# LDM_POWER_PCB.net
KiCad netlist of a schematic drawn in Altium Designer
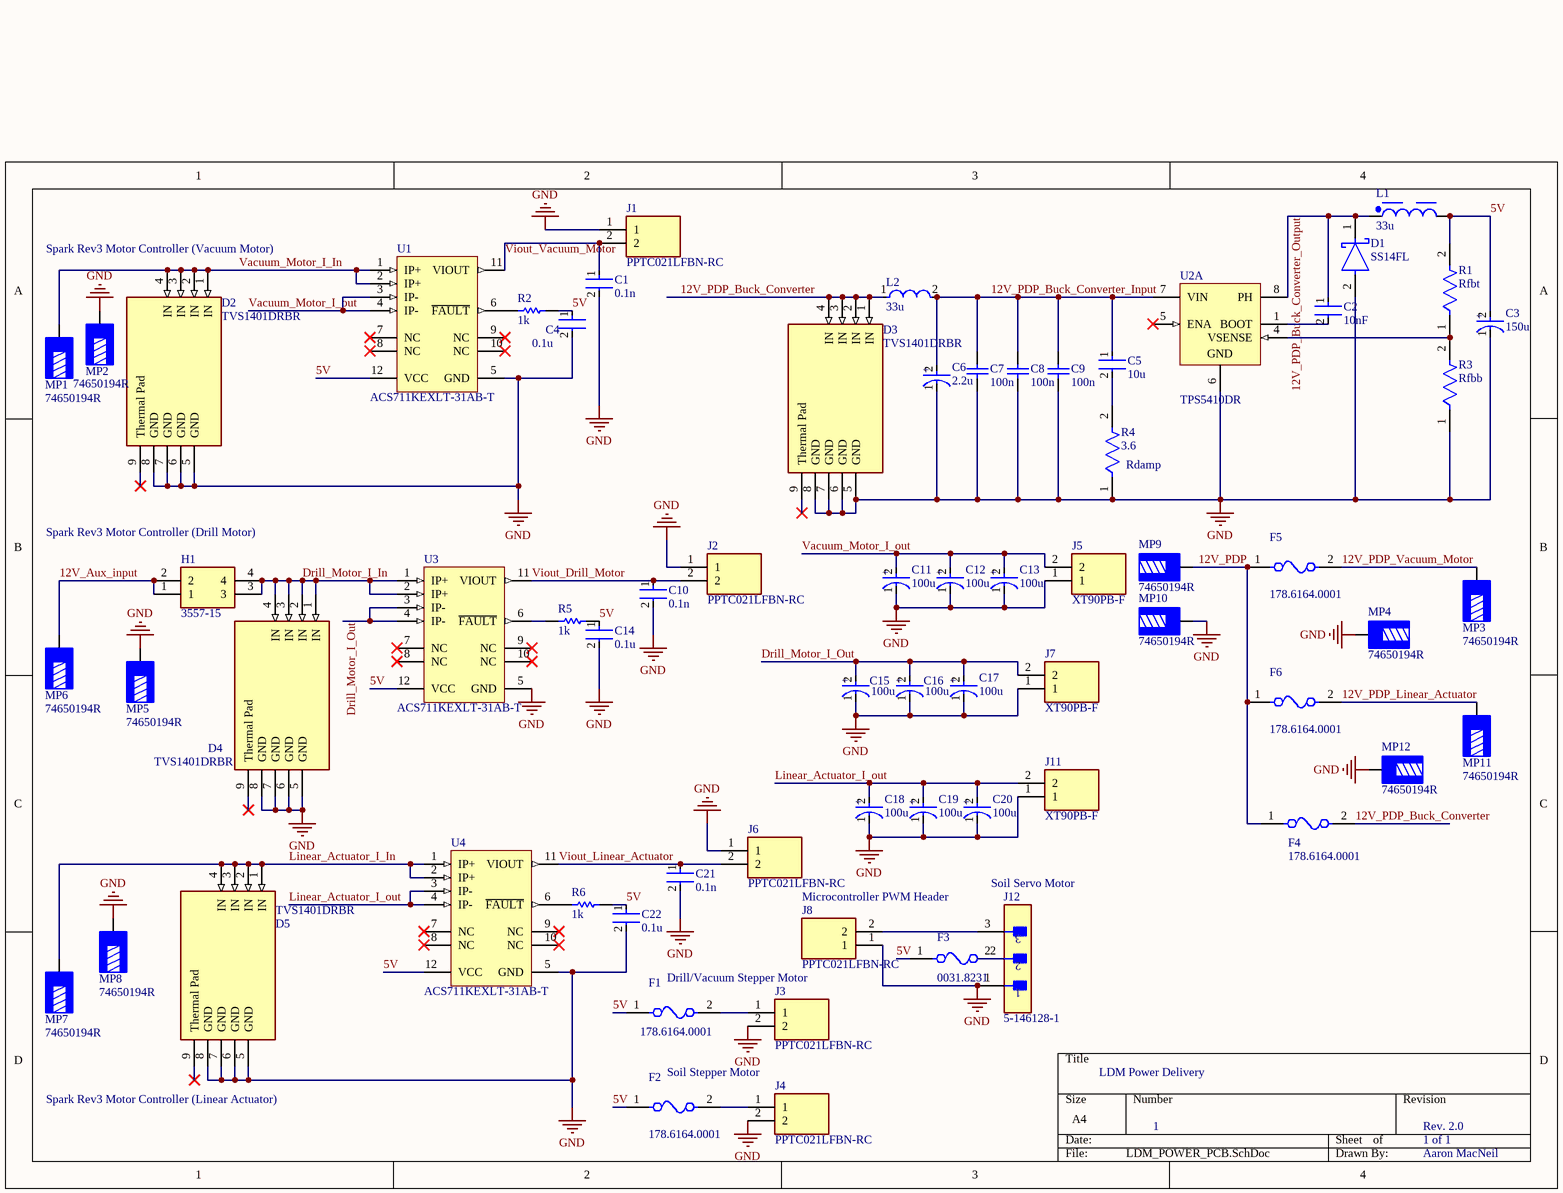
[diagram p0: LDM_POWER_PCB.SchDoc]

(export (version "E")
  (design (tool "Eeschema 10.0.6"))
  (components
    (comp (ref "C1")
      (value "0.1n")
      (footprint "FP-GCM155-0_05-IPC_C")
      (description "Ceramic Capacitor for Automotive 100pF ±5% 50VDC C0G 0402 Paper T/R")
      (fields (field (name "VOLTAGE") "50V") (field (name "TOLERANCE") "5%"))
      (libsource (lib "Altium Content Vault") (part "02cd4be3c70576c341d710602a673aa"))
    )
    (comp (ref "C2")
      (value "10nF")
      (footprint "FP-0805-L_2_01_0_2-W_1_25-IPC_A")
      (description "General Purpose Ceramic Capacitor, 0805, 10nF, 10%, X7R, 0.15, 50V")
      (fields (field (name "TOLERANCE") "10%") (field (name "VOLTAGE") "50V"))
      (libsource (lib "Altium Content Vault") (part "02cd4be3c70576c341d710602a673aa"))
    )
    (comp (ref "C3")
      (value "150u")
      (footprint "FP-POSCAP-B15G-MFG")
      (description "Molded Tantalum Polymer Capacitor 150uF 20% 6.3V life 1000Hours SMD 1411")
      (fields (field (name "TOLERANCE") "20%") (field (name "VOLTAGE") "6.3V"))
      (libsource (lib "Altium Content Vault") (part "203bc49f2ac43e59fd269a8c329ed05"))
    )
    (comp (ref "C4")
      (value "0.1u")
      (footprint "FP-GRM033-0_03-MFG")
      (description "Chip Multilayer Ceramic Capacitors for General Purpose, 0201, 0.10uF, X5R, 15%, 10%, 6.3V")
      (fields (field (name "VOLTAGE") "6.3V") (field (name "TOLERANCE") "10%"))
      (libsource (lib "Altium Content Vault") (part "b4654b650e69147ec39a6b967a45e02"))
    )
    (comp (ref "C5")
      (value "10u")
      (footprint "FP-GRM31C-0_2-e0_3_0_8-MFG")
      (description "Chip Multilayer Ceramic Capacitors for General Purpose, 1206, 10uF, X7R, 15%, 10%, 25V")
      (fields (field (name "TOLERANCE") "10%") (field (name "VOLTAGE") "25V"))
      (libsource (lib "Altium Content Vault") (part "02cd4be3c70576c341d710602a673aa"))
    )
    (comp (ref "C6")
      (value "2.2u")
      (footprint "FP-TAJT-MFG")
      (description "2.2uF 25V  ±10% 4.5Ω 1210  SMD Tantalum Capacitor")
      (fields (field (name "TOLERANCE") "10%"))
      (libsource (lib "Altium Content Vault") (part "203bc49f2ac43e59fd269a8c329ed05"))
    )
    (comp (ref "C7")
      (value "100n")
      (footprint "CAPC2013X145X48NL20T23")
      (fields (field (name "MANUFACTURER") "Vitramon") (field (name "PART NUMBER") "VJ0805Y104KXXAT"))
      (libsource (lib "Altium Content Vault") (part "CAP"))
    )
    (comp (ref "C8")
      (value "100n")
      (footprint "CAPC2013X145X48NL20T23")
      (fields (field (name "MANUFACTURER") "Vitramon") (field (name "PART NUMBER") "VJ0805Y104KXXAT"))
      (libsource (lib "Altium Content Vault") (part "CAP"))
    )
    (comp (ref "C9")
      (value "100n")
      (footprint "CAPC2013X145X48NL20T23")
      (fields (field (name "MANUFACTURER") "Vitramon") (field (name "PART NUMBER") "VJ0805Y104KXXAT"))
      (libsource (lib "Altium Content Vault") (part "CAP"))
    )
    (comp (ref "C10")
      (value "0.1n")
      (footprint "FP-GCM155-0_05-IPC_C")
      (description "Ceramic Capacitor for Automotive 100pF ±5% 50VDC C0G 0402 Paper T/R")
      (fields (field (name "VOLTAGE") "50V") (field (name "TOLERANCE") "5%"))
      (libsource (lib "Altium Content Vault") (part "02cd4be3c70576c341d710602a673aa"))
    )
    (comp (ref "C11")
      (value "100u")
      (footprint "FP-A700X107M12RATE012-MFG")
      (description "ALU POLY SMD 7343 100UF 20% 12.5")
      (fields (field (name "TOLERANCE") "20%"))
      (libsource (lib "Altium Content Vault") (part "cf48714ba7e38822c1575c7ec0b6d1f"))
    )
    (comp (ref "C12")
      (value "100u")
      (footprint "FP-A700X107M12RATE012-MFG")
      (description "ALU POLY SMD 7343 100UF 20% 12.5")
      (fields (field (name "TOLERANCE") "20%"))
      (libsource (lib "Altium Content Vault") (part "cf48714ba7e38822c1575c7ec0b6d1f"))
    )
    (comp (ref "C13")
      (value "100u")
      (footprint "FP-A700X107M12RATE012-MFG")
      (description "ALU POLY SMD 7343 100UF 20% 12.5")
      (fields (field (name "TOLERANCE") "20%"))
      (libsource (lib "Altium Content Vault") (part "cf48714ba7e38822c1575c7ec0b6d1f"))
    )
    (comp (ref "C14")
      (value "0.1u")
      (footprint "FP-GRM033-0_03-MFG")
      (description "Chip Multilayer Ceramic Capacitors for General Purpose, 0201, 0.10uF, X5R, 15%, 10%, 6.3V")
      (fields (field (name "VOLTAGE") "6.3V") (field (name "TOLERANCE") "10%"))
      (libsource (lib "Altium Content Vault") (part "b4654b650e69147ec39a6b967a45e02"))
    )
    (comp (ref "C15")
      (value "100u")
      (footprint "FP-A700X107M12RATE012-MFG")
      (description "ALU POLY SMD 7343 100UF 20% 12.5")
      (fields (field (name "TOLERANCE") "20%"))
      (libsource (lib "Altium Content Vault") (part "cf48714ba7e38822c1575c7ec0b6d1f"))
    )
    (comp (ref "C16")
      (value "100u")
      (footprint "FP-A700X107M12RATE012-MFG")
      (description "ALU POLY SMD 7343 100UF 20% 12.5")
      (fields (field (name "TOLERANCE") "20%"))
      (libsource (lib "Altium Content Vault") (part "cf48714ba7e38822c1575c7ec0b6d1f"))
    )
    (comp (ref "C17")
      (value "100u")
      (footprint "FP-A700X107M12RATE012-MFG")
      (description "ALU POLY SMD 7343 100UF 20% 12.5")
      (fields (field (name "TOLERANCE") "20%"))
      (libsource (lib "Altium Content Vault") (part "cf48714ba7e38822c1575c7ec0b6d1f"))
    )
    (comp (ref "C18")
      (value "100u")
      (footprint "FP-A700X107M12RATE012-MFG")
      (description "ALU POLY SMD 7343 100UF 20% 12.5")
      (fields (field (name "TOLERANCE") "20%"))
      (libsource (lib "Altium Content Vault") (part "cf48714ba7e38822c1575c7ec0b6d1f"))
    )
    (comp (ref "C19")
      (value "100u")
      (footprint "FP-A700X107M12RATE012-MFG")
      (description "ALU POLY SMD 7343 100UF 20% 12.5")
      (fields (field (name "TOLERANCE") "20%"))
      (libsource (lib "Altium Content Vault") (part "cf48714ba7e38822c1575c7ec0b6d1f"))
    )
    (comp (ref "C20")
      (value "100u")
      (footprint "FP-A700X107M12RATE012-MFG")
      (description "ALU POLY SMD 7343 100UF 20% 12.5")
      (fields (field (name "TOLERANCE") "20%"))
      (libsource (lib "Altium Content Vault") (part "cf48714ba7e38822c1575c7ec0b6d1f"))
    )
    (comp (ref "C21")
      (value "0.1n")
      (footprint "FP-GCM155-0_05-IPC_C")
      (description "Ceramic Capacitor for Automotive 100pF ±5% 50VDC C0G 0402 Paper T/R")
      (fields (field (name "VOLTAGE") "50V") (field (name "TOLERANCE") "5%"))
      (libsource (lib "Altium Content Vault") (part "02cd4be3c70576c341d710602a673aa"))
    )
    (comp (ref "C22")
      (value "0.1u")
      (footprint "FP-GRM033-0_03-MFG")
      (description "Chip Multilayer Ceramic Capacitors for General Purpose, 0201, 0.10uF, X5R, 15%, 10%, 6.3V")
      (fields (field (name "VOLTAGE") "6.3V") (field (name "TOLERANCE") "10%"))
      (libsource (lib "Altium Content Vault") (part "b4654b650e69147ec39a6b967a45e02"))
    )
    (comp (ref "D1")
      (value "SS14FL")
      (footprint "FP-425AD-MFG")
      (description "DIODE SCHOTTKY 40V 1A SOD123F")
      (fields
        (field (name "MANUFACTURER") "ON Semiconductor")
        (field (name "OCTOPART") "https://octopart.com/ss14fl-on+semiconductor-84331601")
      )
      (libsource (lib "Altium Content Vault") (part "c1678fac7984e62e0809fbf79c06691"))
    )
    (comp (ref "D2")
      (value "TVS1401DRBR")
      (footprint "FP-DRB0008A-MFG")
      (description "IC UNIDIR PRECISION SURGE DIODE")
      (libsource (lib "Altium Content Vault") (part "760ea3fe8f6653726833b70eb34efed"))
    )
    (comp (ref "D3")
      (value "TVS1401DRBR")
      (footprint "FP-DRB0008A-MFG")
      (description "IC UNIDIR PRECISION SURGE DIODE")
      (libsource (lib "Altium Content Vault") (part "760ea3fe8f6653726833b70eb34efed"))
    )
    (comp (ref "D4")
      (value "TVS1401DRBR")
      (footprint "FP-DRB0008A-MFG")
      (description "IC UNIDIR PRECISION SURGE DIODE")
      (libsource (lib "Altium Content Vault") (part "760ea3fe8f6653726833b70eb34efed"))
    )
    (comp (ref "D5")
      (value "TVS1401DRBR")
      (footprint "FP-DRB0008A-MFG")
      (description "IC UNIDIR PRECISION SURGE DIODE")
      (libsource (lib "Altium Content Vault") (part "760ea3fe8f6653726833b70eb34efed"))
    )
    (comp (ref "F1")
      (value "178.6164.0001")
      (footprint "FP-178_6164_0001-MFG")
      (description "FUSE HOLDER BLADE 80V PCB")
      (fields
        (field (name "MANUFACTURER") "Littelfuse Inc")
        (field (name "OCTOPART") "https://octopart.com/178.6164.0001-littelfuse-44502275")
      )
      (libsource (lib "Altium Content Vault") (part "5bcf9b9f640e542cf0359d10258e979"))
    )
    (comp (ref "F2")
      (value "178.6164.0001")
      (footprint "FP-178_6164_0001-MFG")
      (description "FUSE HOLDER BLADE 80V PCB")
      (fields
        (field (name "MANUFACTURER") "Littelfuse Inc")
        (field (name "OCTOPART") "https://octopart.com/178.6164.0001-littelfuse-44502275")
      )
      (libsource (lib "Altium Content Vault") (part "5bcf9b9f640e542cf0359d10258e979"))
    )
    (comp (ref "F3")
      (value "0031.8231")
      (footprint "FP-0031_8231-MFG")
      (description "FUSE BLOK CARTRIDGE 600V 16A PCB")
      (fields
        (field (name "OCTOPART") "https://octopart.com/0031.8231-schurter-8659")
        (field (name "MANUFACTURER") "Schurter")
      )
      (libsource (lib "Altium Content Vault") (part "5bcf9b9f640e542cf0359d10258e979"))
    )
    (comp (ref "F4")
      (value "178.6164.0001")
      (footprint "FP-178_6164_0001-MFG")
      (description "FUSE HOLDER BLADE 80V PCB")
      (fields
        (field (name "MANUFACTURER") "Littelfuse Inc")
        (field (name "OCTOPART") "https://octopart.com/178.6164.0001-littelfuse-44502275")
      )
      (libsource (lib "Altium Content Vault") (part "5bcf9b9f640e542cf0359d10258e979"))
    )
    (comp (ref "F5")
      (value "178.6164.0001")
      (footprint "FP-178_6164_0001-MFG")
      (description "FUSE HOLDER BLADE 80V PCB")
      (fields
        (field (name "MANUFACTURER") "Littelfuse Inc")
        (field (name "OCTOPART") "https://octopart.com/178.6164.0001-littelfuse-44502275")
      )
      (libsource (lib "Altium Content Vault") (part "5bcf9b9f640e542cf0359d10258e979"))
    )
    (comp (ref "F6")
      (value "178.6164.0001")
      (footprint "FP-178_6164_0001-MFG")
      (description "FUSE HOLDER BLADE 80V PCB")
      (fields
        (field (name "MANUFACTURER") "Littelfuse Inc")
        (field (name "OCTOPART") "https://octopart.com/178.6164.0001-littelfuse-44502275")
      )
      (libsource (lib "Altium Content Vault") (part "5bcf9b9f640e542cf0359d10258e979"))
    )
    (comp (ref "H1")
      (value "3557-15")
      (footprint "SamacSys:355715")
      (description "Hardware")
      (fields (field (name "MOUSER PART NUMBER") "534-3557-15"))
      (libsource (lib "*") (part "3557-15"))
    )
    (comp (ref "J1")
      (value "PPTC021LFBN-RC")
      (footprint "SamacSys:RHDR2W80P0X254_1X2_558X254X850P")
      (description "Connector")
      (libsource (lib "*") (part "PPTC021LFBN-RC"))
    )
    (comp (ref "J2")
      (value "PPTC021LFBN-RC")
      (footprint "SamacSys:RHDR2W80P0X254_1X2_558X254X850P")
      (description "Connector")
      (libsource (lib "*") (part "PPTC021LFBN-RC"))
    )
    (comp (ref "J3")
      (value "PPTC021LFBN-RC")
      (footprint "SamacSys:RHDR2W80P0X254_1X2_558X254X850P")
      (description "Connector")
      (libsource (lib "*") (part "PPTC021LFBN-RC"))
    )
    (comp (ref "J4")
      (value "PPTC021LFBN-RC")
      (footprint "SamacSys:RHDR2W80P0X254_1X2_558X254X850P")
      (description "Connector")
      (libsource (lib "*") (part "PPTC021LFBN-RC"))
    )
    (comp (ref "J5")
      (value "XT90PB-F")
      (footprint "SamacSys:XT90PBF")
      (description "Connector")
      (libsource (lib "*") (part "XT90PB-F"))
    )
    (comp (ref "J6")
      (value "PPTC021LFBN-RC")
      (footprint "SamacSys:RHDR2W80P0X254_1X2_558X254X850P")
      (description "Connector")
      (libsource (lib "*") (part "PPTC021LFBN-RC"))
    )
    (comp (ref "J7")
      (value "XT90PB-F")
      (footprint "SamacSys:XT90PBF")
      (description "Connector")
      (libsource (lib "*") (part "XT90PB-F"))
    )
    (comp (ref "J8")
      (value "PPTC021LFBN-RC")
      (footprint "SamacSys:RHDR2W80P0X254_1X2_558X254X850P")
      (description "Connector")
      (libsource (lib "") (part "PPTC021LFBN-RC_1"))
    )
    (comp (ref "J11")
      (value "XT90PB-F")
      (footprint "SamacSys:XT90PBF")
      (description "Connector")
      (libsource (lib "*") (part "XT90PB-F"))
    )
    (comp (ref "J12")
      (value "5-146128-1")
      (footprint "FP-5-146128-1-MFG")
      (description "CONN HEADER SMD 3POS 2.54MM")
      (fields
        (field (name "MANUFACTURER") "TE")
        (field (name "OCTOPART") "https://octopart.com/5-146128-1-te+connectivity-40948200")
      )
      (libsource (lib "Altium Content Vault") (part "0d3f023dd272f625e17a2be33dea85f"))
    )
    (comp (ref "L1")
      (value "33u")
      (footprint "WE-LQS_6045")
      (fields (field (name "TOLERANCE") "20%"))
      (libsource (lib "Altium Content Vault") (part "Inductor - 2"))
    )
    (comp (ref "L2")
      (value "33u")
      (footprint "FP-NR6028-MFG")
      (description "SMD Power Inductors 33uH ±20% 1.1A 0.286Ω")
      (fields (field (name "TOLERANCE") "20%"))
      (libsource (lib "Altium Content Vault") (part "725321dda6339637d4d059423bc1c3c"))
    )
    (comp (ref "MP1")
      (value "74650194R")
      (footprint "74650194")
      (description "74650194R Bush, THR, internal blind-hole thread, 10 mm W x 7 mm H, M4, 9 Pins")
      (libsource (lib "Altium Content Vault") (part "WP-THRBU_blind hole"))
    )
    (comp (ref "MP2")
      (value "74650194R")
      (footprint "74650194")
      (description "74650194R Bush, THR, internal blind-hole thread, 10 mm W x 7 mm H, M4, 9 Pins")
      (libsource (lib "Altium Content Vault") (part "WP-THRBU_blind hole"))
    )
    (comp (ref "MP3")
      (value "74650194R")
      (footprint "74650194")
      (description "74650194R Bush, THR, internal blind-hole thread, 10 mm W x 7 mm H, M4, 9 Pins")
      (libsource (lib "Altium Content Vault") (part "WP-THRBU_blind hole"))
    )
    (comp (ref "MP4")
      (value "74650194R")
      (footprint "74650194")
      (description "74650194R Bush, THR, internal blind-hole thread, 10 mm W x 7 mm H, M4, 9 Pins")
      (libsource (lib "Altium Content Vault") (part "WP-THRBU_blind hole"))
    )
    (comp (ref "MP5")
      (value "74650194R")
      (footprint "74650194")
      (description "74650194R Bush, THR, internal blind-hole thread, 10 mm W x 7 mm H, M4, 9 Pins")
      (libsource (lib "Altium Content Vault") (part "WP-THRBU_blind hole"))
    )
    (comp (ref "MP6")
      (value "74650194R")
      (footprint "74650194")
      (description "74650194R Bush, THR, internal blind-hole thread, 10 mm W x 7 mm H, M4, 9 Pins")
      (libsource (lib "Altium Content Vault") (part "WP-THRBU_blind hole"))
    )
    (comp (ref "MP7")
      (value "74650194R")
      (footprint "74650194")
      (description "74650194R Bush, THR, internal blind-hole thread, 10 mm W x 7 mm H, M4, 9 Pins")
      (libsource (lib "Altium Content Vault") (part "WP-THRBU_blind hole"))
    )
    (comp (ref "MP8")
      (value "74650194R")
      (footprint "74650194")
      (description "74650194R Bush, THR, internal blind-hole thread, 10 mm W x 7 mm H, M4, 9 Pins")
      (libsource (lib "Altium Content Vault") (part "WP-THRBU_blind hole"))
    )
    (comp (ref "MP9")
      (value "74650194R")
      (footprint "74650194")
      (description "74650194R Bush, THR, internal blind-hole thread, 10 mm W x 7 mm H, M4, 9 Pins")
      (libsource (lib "Altium Content Vault") (part "WP-THRBU_blind hole"))
    )
    (comp (ref "MP10")
      (value "74650194R")
      (footprint "74650194")
      (description "74650194R Bush, THR, internal blind-hole thread, 10 mm W x 7 mm H, M4, 9 Pins")
      (libsource (lib "Altium Content Vault") (part "WP-THRBU_blind hole"))
    )
    (comp (ref "MP11")
      (value "74650194R")
      (footprint "74650194")
      (description "74650194R Bush, THR, internal blind-hole thread, 10 mm W x 7 mm H, M4, 9 Pins")
      (libsource (lib "Altium Content Vault") (part "WP-THRBU_blind hole"))
    )
    (comp (ref "MP12")
      (value "74650194R")
      (footprint "74650194")
      (description "74650194R Bush, THR, internal blind-hole thread, 10 mm W x 7 mm H, M4, 9 Pins")
      (libsource (lib "Altium Content Vault") (part "WP-THRBU_blind hole"))
    )
    (comp (ref "R1")
      (value "Rfbt")
      (footprint "FP-CRCW0402-e3-IPC_B")
      (description "RES SMD 10K OHM 1% 1/16W 0402")
      (fields (field (name "TOLERANCE") "1%"))
      (libsource (lib "Altium Content Vault") (part "1029c3af85768c4190bb7ad29bc67b5"))
    )
    (comp (ref "R2")
      (value "1k")
      (footprint "RESC1608X55X30LL15T15")
      (fields (field (name "PART NUMBER") "ERJ-3EKF1001V") (field (name "MANUFACTURER") "Panasonic"))
      (libsource (lib "Altium Content Vault") (part "RES"))
    )
    (comp (ref "R3")
      (value "Rfbb")
      (footprint "FP-CRCW0402-e3-MFG")
      (description "RES Thick Film, 3.24kΩ, 1%, 0.063W, 100ppm/°C, 0402")
      (fields (field (name "TOLERANCE") "1%"))
      (libsource (lib "Altium Content Vault") (part "1029c3af85768c4190bb7ad29bc67b5"))
    )
    (comp (ref "R4")
      (value "3.6")
      (footprint "FP-ESR10-IPC_A")
      (description "3.6Ω ±5% 0.4W 0805 Anti-Surge Chip Resistor AEC-Q200")
      (fields (field (name "TOLERANCE") "5%"))
      (libsource (lib "Altium Content Vault") (part "1029c3af85768c4190bb7ad29bc67b5"))
    )
    (comp (ref "R5")
      (value "1k")
      (footprint "RESC1608X55X30LL15T15")
      (fields (field (name "PART NUMBER") "ERJ-3EKF1001V") (field (name "MANUFACTURER") "Panasonic"))
      (libsource (lib "Altium Content Vault") (part "RES"))
    )
    (comp (ref "R6")
      (value "1k")
      (footprint "RESC1608X55X30LL15T15")
      (fields (field (name "PART NUMBER") "ERJ-3EKF1001V") (field (name "MANUFACTURER") "Panasonic"))
      (libsource (lib "Altium Content Vault") (part "RES"))
    )
    (comp (ref "U1")
      (value "ACS711KEXLT-31AB-T")
      (footprint "ALEG-EX-12_V")
      (libsource (lib "Altium Content Vault") (part "ALEG-ACS711-QFN-12"))
    )
    (comp (ref "U2")
      (value "TPS5410DR")
      (footprint "D0008A_L")
      (fields (field (name "MANUFACTURER") "Texas Instruments"))
      (libsource (lib "Altium Content Vault") (part "TI-TPS5410D8"))
    )
    (comp (ref "U3")
      (value "ACS711KEXLT-31AB-T")
      (footprint "ALEG-EX-12_V")
      (libsource (lib "Altium Content Vault") (part "ALEG-ACS711-QFN-12"))
    )
    (comp (ref "U4")
      (value "ACS711KEXLT-31AB-T")
      (footprint "ALEG-EX-12_V")
      (libsource (lib "Altium Content Vault") (part "ALEG-ACS711-QFN-12"))
    )
  )
  (nets
    (net (code "1") (name "/5V") (class "Default")
      (node (ref "C14") (pin "1") (pinfunction "1_1") (pintype "passive"))
      (node (ref "C22") (pin "1") (pinfunction "1_1") (pintype "passive"))
      (node (ref "C3") (pin "2") (pinfunction "A_2") (pintype "passive"))
      (node (ref "C4") (pin "1") (pinfunction "1_1") (pintype "passive"))
      (node (ref "F1") (pin "1") (pinfunction "1_1") (pintype "passive"))
      (node (ref "F2") (pin "1") (pinfunction "1_1") (pintype "passive"))
      (node (ref "F3") (pin "1") (pinfunction "1_1") (pintype "passive"))
      (node (ref "L1") (pin "2") (pinfunction "2_2") (pintype "passive"))
      (node (ref "R1") (pin "2") (pinfunction "2_2") (pintype "passive"))
      (node (ref "R2") (pin "2") (pinfunction "2_2") (pintype "passive"))
      (node (ref "R5") (pin "2") (pinfunction "2_2") (pintype "passive"))
      (node (ref "R6") (pin "2") (pinfunction "2_2") (pintype "passive"))
      (node (ref "U1") (pin "12") (pinfunction "VCC_12") (pintype "power_in"))
      (node (ref "U3") (pin "12") (pinfunction "VCC_12") (pintype "power_in"))
      (node (ref "U4") (pin "12") (pinfunction "VCC_12") (pintype "power_in"))
    )
    (net (code "2") (name "/12V_Aux_input") (class "Default")
      (node (ref "H1") (pin "1") (pinfunction "1_1") (pintype "passive"))
      (node (ref "H1") (pin "2") (pinfunction "2_2") (pintype "passive"))
      (node (ref "MP6") (pin "1") (pinfunction "1_1") (pintype "passive"))
    )
    (net (code "3") (name "/12V_PDP") (class "Default")
      (node (ref "F4") (pin "1") (pinfunction "1_1") (pintype "passive"))
      (node (ref "F5") (pin "1") (pinfunction "1_1") (pintype "passive"))
      (node (ref "F6") (pin "1") (pinfunction "1_1") (pintype "passive"))
      (node (ref "MP9") (pin "1") (pinfunction "1_1") (pintype "passive"))
    )
    (net (code "4") (name "/12V_PDP_Buck_Converter") (class "Default")
      (node (ref "D3") (pin "1") (pinfunction "IN_1") (pintype "input"))
      (node (ref "D3") (pin "2") (pinfunction "IN_2") (pintype "input"))
      (node (ref "D3") (pin "3") (pinfunction "IN_3") (pintype "input"))
      (node (ref "D3") (pin "4") (pinfunction "IN_4") (pintype "input"))
      (node (ref "F4") (pin "2") (pinfunction "2_2") (pintype "passive"))
      (node (ref "L2") (pin "1") (pinfunction "1_1") (pintype "passive"))
    )
    (net (code "5") (name "/12V_PDP_Buck_Converter_Input") (class "Default")
      (node (ref "C5") (pin "1") (pinfunction "1_1") (pintype "passive"))
      (node (ref "C6") (pin "2") (pinfunction "A_2") (pintype "passive"))
      (node (ref "C7") (pin "2") (pinfunction "2_2") (pintype "passive"))
      (node (ref "C8") (pin "2") (pinfunction "2_2") (pintype "passive"))
      (node (ref "C9") (pin "2") (pinfunction "2_2") (pintype "passive"))
      (node (ref "L2") (pin "2") (pinfunction "2_2") (pintype "passive"))
      (node (ref "U2") (pin "7") (pinfunction "VIN_7") (pintype "power_in"))
    )
    (net (code "6") (name "/12V_PDP_Buck_Converter_Output") (class "Default")
      (node (ref "C2") (pin "1") (pinfunction "1_1") (pintype "passive"))
      (node (ref "D1") (pin "1") (pinfunction "C_1") (pintype "passive"))
      (node (ref "L1") (pin "1") (pinfunction "1_1") (pintype "passive"))
      (node (ref "U2") (pin "8") (pinfunction "PH_8") (pintype "power_in"))
    )
    (net (code "7") (name "/12V_PDP_Linear_Actuator") (class "Default")
      (node (ref "F6") (pin "2") (pinfunction "2_2") (pintype "passive"))
      (node (ref "MP11") (pin "1") (pinfunction "1_1") (pintype "passive"))
    )
    (net (code "8") (name "/12V_PDP_Vacuum_Motor") (class "Default")
      (node (ref "F5") (pin "2") (pinfunction "2_2") (pintype "passive"))
      (node (ref "MP3") (pin "1") (pinfunction "1_1") (pintype "passive"))
    )
    (net (code "9") (name "/Drill_Motor_I_In") (class "Default")
      (node (ref "D4") (pin "1") (pinfunction "IN_1") (pintype "input"))
      (node (ref "D4") (pin "2") (pinfunction "IN_2") (pintype "input"))
      (node (ref "D4") (pin "3") (pinfunction "IN_3") (pintype "input"))
      (node (ref "D4") (pin "4") (pinfunction "IN_4") (pintype "input"))
      (node (ref "H1") (pin "3") (pinfunction "3_3") (pintype "passive"))
      (node (ref "H1") (pin "4") (pinfunction "4_4") (pintype "passive"))
      (node (ref "U3") (pin "1") (pinfunction "IP+_1") (pintype "input"))
      (node (ref "U3") (pin "2") (pinfunction "IP+_2") (pintype "input"))
    )
    (net (code "10") (name "/Drill_Motor_I_Out") (class "Default")
      (node (ref "C15") (pin "2") (pinfunction "A_2") (pintype "passive"))
      (node (ref "C16") (pin "2") (pinfunction "A_2") (pintype "passive"))
      (node (ref "C17") (pin "2") (pinfunction "A_2") (pintype "passive"))
      (node (ref "J7") (pin "2") (pinfunction "2_2") (pintype "passive"))
      (node (ref "U3") (pin "3") (pinfunction "IP-_3") (pintype "input"))
      (node (ref "U3") (pin "4") (pinfunction "IP-_4") (pintype "input"))
    )
    (net (code "11") (name "/Linear_Actuator_I_In") (class "Default")
      (node (ref "D5") (pin "1") (pinfunction "IN_1") (pintype "input"))
      (node (ref "D5") (pin "2") (pinfunction "IN_2") (pintype "input"))
      (node (ref "D5") (pin "3") (pinfunction "IN_3") (pintype "input"))
      (node (ref "D5") (pin "4") (pinfunction "IN_4") (pintype "input"))
      (node (ref "MP7") (pin "1") (pinfunction "1_1") (pintype "passive"))
      (node (ref "U4") (pin "1") (pinfunction "IP+_1") (pintype "input"))
      (node (ref "U4") (pin "2") (pinfunction "IP+_2") (pintype "input"))
    )
    (net (code "12") (name "/Linear_Actuator_I_out") (class "Default")
      (node (ref "C18") (pin "2") (pinfunction "A_2") (pintype "passive"))
      (node (ref "C19") (pin "2") (pinfunction "A_2") (pintype "passive"))
      (node (ref "C20") (pin "2") (pinfunction "A_2") (pintype "passive"))
      (node (ref "J11") (pin "2") (pinfunction "2_2") (pintype "passive"))
      (node (ref "U4") (pin "3") (pinfunction "IP-_3") (pintype "input"))
      (node (ref "U4") (pin "4") (pinfunction "IP-_4") (pintype "input"))
    )
    (net (code "13") (name "/Vacuum_Motor_I_In") (class "Default")
      (node (ref "D2") (pin "1") (pinfunction "IN_1") (pintype "input"))
      (node (ref "D2") (pin "2") (pinfunction "IN_2") (pintype "input"))
      (node (ref "D2") (pin "3") (pinfunction "IN_3") (pintype "input"))
      (node (ref "D2") (pin "4") (pinfunction "IN_4") (pintype "input"))
      (node (ref "MP1") (pin "1") (pinfunction "1_1") (pintype "passive"))
      (node (ref "U1") (pin "1") (pinfunction "IP+_1") (pintype "input"))
      (node (ref "U1") (pin "2") (pinfunction "IP+_2") (pintype "input"))
    )
    (net (code "14") (name "/Vacuum_Motor_I_out") (class "Default")
      (node (ref "C11") (pin "2") (pinfunction "A_2") (pintype "passive"))
      (node (ref "C12") (pin "2") (pinfunction "A_2") (pintype "passive"))
      (node (ref "C13") (pin "2") (pinfunction "A_2") (pintype "passive"))
      (node (ref "J5") (pin "2") (pinfunction "2_2") (pintype "passive"))
      (node (ref "U1") (pin "3") (pinfunction "IP-_3") (pintype "input"))
      (node (ref "U1") (pin "4") (pinfunction "IP-_4") (pintype "input"))
    )
    (net (code "15") (name "/Viout_Drill_Motor") (class "Default")
      (node (ref "C10") (pin "1") (pinfunction "1_1") (pintype "passive"))
      (node (ref "J2") (pin "2") (pinfunction "2_2") (pintype "passive"))
      (node (ref "U3") (pin "11") (pinfunction "VIOUT_11") (pintype "output"))
    )
    (net (code "16") (name "/Viout_Linear_Actuator") (class "Default")
      (node (ref "C21") (pin "1") (pinfunction "1_1") (pintype "passive"))
      (node (ref "J6") (pin "2") (pinfunction "2_2") (pintype "passive"))
      (node (ref "U4") (pin "11") (pinfunction "VIOUT_11") (pintype "output"))
    )
    (net (code "17") (name "/Viout_Vacuum_Motor") (class "Default")
      (node (ref "C1") (pin "1") (pinfunction "1_1") (pintype "passive"))
      (node (ref "J1") (pin "2") (pinfunction "2_2") (pintype "passive"))
      (node (ref "U1") (pin "11") (pinfunction "VIOUT_11") (pintype "output"))
    )
    (net (code "18") (name "GND") (class "Default")
      (node (ref "C1") (pin "2") (pinfunction "2_2") (pintype "passive"))
      (node (ref "C10") (pin "2") (pinfunction "2_2") (pintype "passive"))
      (node (ref "C11") (pin "1") (pinfunction "C_1") (pintype "passive"))
      (node (ref "C12") (pin "1") (pinfunction "C_1") (pintype "passive"))
      (node (ref "C13") (pin "1") (pinfunction "C_1") (pintype "passive"))
      (node (ref "C14") (pin "2") (pinfunction "2_2") (pintype "passive"))
      (node (ref "C15") (pin "1") (pinfunction "C_1") (pintype "passive"))
      (node (ref "C16") (pin "1") (pinfunction "C_1") (pintype "passive"))
      (node (ref "C17") (pin "1") (pinfunction "C_1") (pintype "passive"))
      (node (ref "C18") (pin "1") (pinfunction "C_1") (pintype "passive"))
      (node (ref "C19") (pin "1") (pinfunction "C_1") (pintype "passive"))
      (node (ref "C20") (pin "1") (pinfunction "C_1") (pintype "passive"))
      (node (ref "C21") (pin "2") (pinfunction "2_2") (pintype "passive"))
      (node (ref "C22") (pin "2") (pinfunction "2_2") (pintype "passive"))
      (node (ref "C3") (pin "1") (pinfunction "C_1") (pintype "passive"))
      (node (ref "C4") (pin "2") (pinfunction "2_2") (pintype "passive"))
      (node (ref "C6") (pin "1") (pinfunction "C_1") (pintype "passive"))
      (node (ref "C7") (pin "1") (pinfunction "1_1") (pintype "passive"))
      (node (ref "C8") (pin "1") (pinfunction "1_1") (pintype "passive"))
      (node (ref "C9") (pin "1") (pinfunction "1_1") (pintype "passive"))
      (node (ref "D1") (pin "2") (pinfunction "A_2") (pintype "passive"))
      (node (ref "D2") (pin "5") (pinfunction "GND_5") (pintype "power_in"))
      (node (ref "D2") (pin "6") (pinfunction "GND_6") (pintype "power_in"))
      (node (ref "D2") (pin "7") (pinfunction "GND_7") (pintype "power_in"))
      (node (ref "D2") (pin "8") (pinfunction "GND_8") (pintype "power_in"))
      (node (ref "D3") (pin "5") (pinfunction "GND_5") (pintype "power_in"))
      (node (ref "D3") (pin "6") (pinfunction "GND_6") (pintype "power_in"))
      (node (ref "D3") (pin "7") (pinfunction "GND_7") (pintype "power_in"))
      (node (ref "D3") (pin "8") (pinfunction "GND_8") (pintype "power_in"))
      (node (ref "D4") (pin "5") (pinfunction "GND_5") (pintype "power_in"))
      (node (ref "D4") (pin "6") (pinfunction "GND_6") (pintype "power_in"))
      (node (ref "D4") (pin "7") (pinfunction "GND_7") (pintype "power_in"))
      (node (ref "D4") (pin "8") (pinfunction "GND_8") (pintype "power_in"))
      (node (ref "D5") (pin "5") (pinfunction "GND_5") (pintype "power_in"))
      (node (ref "D5") (pin "6") (pinfunction "GND_6") (pintype "power_in"))
      (node (ref "D5") (pin "7") (pinfunction "GND_7") (pintype "power_in"))
      (node (ref "D5") (pin "8") (pinfunction "GND_8") (pintype "power_in"))
      (node (ref "J1") (pin "1") (pinfunction "1_1") (pintype "passive"))
      (node (ref "J11") (pin "1") (pinfunction "1_1") (pintype "passive"))
      (node (ref "J12") (pin "1") (pinfunction "1_1") (pintype "passive"))
      (node (ref "J2") (pin "1") (pinfunction "1_1") (pintype "passive"))
      (node (ref "J3") (pin "2") (pinfunction "2_2") (pintype "passive"))
      (node (ref "J4") (pin "2") (pinfunction "2_2") (pintype "passive"))
      (node (ref "J5") (pin "1") (pinfunction "1_1") (pintype "passive"))
      (node (ref "J6") (pin "1") (pinfunction "1_1") (pintype "passive"))
      (node (ref "J7") (pin "1") (pinfunction "1_1") (pintype "passive"))
      (node (ref "J8") (pin "1") (pinfunction "1_1") (pintype "passive"))
      (node (ref "MP10") (pin "1") (pinfunction "1_1") (pintype "passive"))
      (node (ref "MP12") (pin "1") (pinfunction "1_1") (pintype "passive"))
      (node (ref "MP2") (pin "1") (pinfunction "1_1") (pintype "passive"))
      (node (ref "MP4") (pin "1") (pinfunction "1_1") (pintype "passive"))
      (node (ref "MP5") (pin "1") (pinfunction "1_1") (pintype "passive"))
      (node (ref "MP8") (pin "1") (pinfunction "1_1") (pintype "passive"))
      (node (ref "R3") (pin "1") (pinfunction "1_1") (pintype "passive"))
      (node (ref "R4") (pin "1") (pinfunction "1_1") (pintype "passive"))
      (node (ref "U1") (pin "5") (pinfunction "GND_5") (pintype "power_in"))
      (node (ref "U2") (pin "6") (pinfunction "GND_6") (pintype "power_in"))
      (node (ref "U3") (pin "5") (pinfunction "GND_5") (pintype "power_in"))
      (node (ref "U4") (pin "5") (pinfunction "GND_5") (pintype "power_in"))
    )
    (net (code "19") (name "Net-(C5-Pad2)") (class "Default")
      (node (ref "C5") (pin "2") (pinfunction "2_2") (pintype "passive"))
      (node (ref "R4") (pin "2") (pinfunction "2_2") (pintype "passive"))
    )
    (net (code "20") (name "Net-(F1-Pad2)") (class "Default")
      (node (ref "F1") (pin "2") (pinfunction "2_2") (pintype "passive"))
      (node (ref "J3") (pin "1") (pinfunction "1_1") (pintype "passive"))
    )
    (net (code "21") (name "Net-(F2-Pad2)") (class "Default")
      (node (ref "F2") (pin "2") (pinfunction "2_2") (pintype "passive"))
      (node (ref "J4") (pin "1") (pinfunction "1_1") (pintype "passive"))
    )
    (net (code "22") (name "Net-(F3-Pad2)") (class "Default")
      (node (ref "F3") (pin "2") (pinfunction "2_2") (pintype "passive"))
      (node (ref "J12") (pin "2") (pinfunction "2_2") (pintype "passive"))
    )
    (net (code "23") (name "Net-(J12-Pad3)") (class "Default")
      (node (ref "J12") (pin "3") (pinfunction "3_3") (pintype "passive"))
      (node (ref "J8") (pin "2") (pinfunction "2_2") (pintype "passive"))
    )
    (net (code "24") (name "Net-(U1-~{FAULT})") (class "Default")
      (node (ref "R2") (pin "1") (pinfunction "1_1") (pintype "passive"))
      (node (ref "U1") (pin "6") (pinfunction "~{FAULT}_6") (pintype "output"))
    )
    (net (code "25") (name "Net-(U2A-BOOT)") (class "Default")
      (node (ref "C2") (pin "2") (pinfunction "2_2") (pintype "passive"))
      (node (ref "U2") (pin "1") (pinfunction "BOOT_1") (pintype "passive"))
    )
    (net (code "26") (name "Net-(U2A-VSENSE)") (class "Default")
      (node (ref "R1") (pin "1") (pinfunction "1_1") (pintype "passive"))
      (node (ref "R3") (pin "2") (pinfunction "2_2") (pintype "passive"))
      (node (ref "U2") (pin "4") (pinfunction "VSENSE_4") (pintype "input"))
    )
    (net (code "27") (name "Net-(U3-~{FAULT})") (class "Default")
      (node (ref "R5") (pin "1") (pinfunction "1_1") (pintype "passive"))
      (node (ref "U3") (pin "6") (pinfunction "~{FAULT}_6") (pintype "output"))
    )
    (net (code "28") (name "Net-(U4-~{FAULT})") (class "Default")
      (node (ref "R6") (pin "1") (pinfunction "1_1") (pintype "passive"))
      (node (ref "U4") (pin "6") (pinfunction "~{FAULT}_6") (pintype "output"))
    )
    (net (code "29") (name "unconnected-(D2-Thermal_Pad-Pad9)") (class "Default")
      (node (ref "D2") (pin "9") (pinfunction "Thermal_Pad_9") (pintype "power_in+no_connect"))
    )
    (net (code "30") (name "unconnected-(D3-Thermal_Pad-Pad9)") (class "Default")
      (node (ref "D3") (pin "9") (pinfunction "Thermal_Pad_9") (pintype "power_in+no_connect"))
    )
    (net (code "31") (name "unconnected-(D4-Thermal_Pad-Pad9)") (class "Default")
      (node (ref "D4") (pin "9") (pinfunction "Thermal_Pad_9") (pintype "power_in+no_connect"))
    )
    (net (code "32") (name "unconnected-(D5-Thermal_Pad-Pad9)") (class "Default")
      (node (ref "D5") (pin "9") (pinfunction "Thermal_Pad_9") (pintype "power_in+no_connect"))
    )
    (net (code "33") (name "unconnected-(U1-NC-Pad7)") (class "Default")
      (node (ref "U1") (pin "7") (pinfunction "NC_7") (pintype "passive+no_connect"))
    )
    (net (code "34") (name "unconnected-(U1-NC-Pad8)") (class "Default")
      (node (ref "U1") (pin "8") (pinfunction "NC_8") (pintype "passive+no_connect"))
    )
    (net (code "35") (name "unconnected-(U1-NC-Pad9)") (class "Default")
      (node (ref "U1") (pin "9") (pinfunction "NC_9") (pintype "passive+no_connect"))
    )
    (net (code "36") (name "unconnected-(U1-NC-Pad10)") (class "Default")
      (node (ref "U1") (pin "10") (pinfunction "NC_10") (pintype "passive+no_connect"))
    )
    (net (code "37") (name "unconnected-(U2A-ENA-Pad5)") (class "Default")
      (node (ref "U2") (pin "5") (pinfunction "ENA_5") (pintype "input+no_connect"))
    )
    (net (code "38") (name "unconnected-(U3-NC-Pad7)") (class "Default")
      (node (ref "U3") (pin "7") (pinfunction "NC_7") (pintype "passive+no_connect"))
    )
    (net (code "39") (name "unconnected-(U3-NC-Pad8)") (class "Default")
      (node (ref "U3") (pin "8") (pinfunction "NC_8") (pintype "passive+no_connect"))
    )
    (net (code "40") (name "unconnected-(U3-NC-Pad9)") (class "Default")
      (node (ref "U3") (pin "9") (pinfunction "NC_9") (pintype "passive+no_connect"))
    )
    (net (code "41") (name "unconnected-(U3-NC-Pad10)") (class "Default")
      (node (ref "U3") (pin "10") (pinfunction "NC_10") (pintype "passive+no_connect"))
    )
    (net (code "42") (name "unconnected-(U4-NC-Pad7)") (class "Default")
      (node (ref "U4") (pin "7") (pinfunction "NC_7") (pintype "passive+no_connect"))
    )
    (net (code "43") (name "unconnected-(U4-NC-Pad8)") (class "Default")
      (node (ref "U4") (pin "8") (pinfunction "NC_8") (pintype "passive+no_connect"))
    )
    (net (code "44") (name "unconnected-(U4-NC-Pad9)") (class "Default")
      (node (ref "U4") (pin "9") (pinfunction "NC_9") (pintype "passive+no_connect"))
    )
    (net (code "45") (name "unconnected-(U4-NC-Pad10)") (class "Default")
      (node (ref "U4") (pin "10") (pinfunction "NC_10") (pintype "passive+no_connect"))
    )
  )
)
